# SCH_Dual_voltage_converter_2022-07-17.net
KiCad netlist of a schematic drawn in EasyEDA
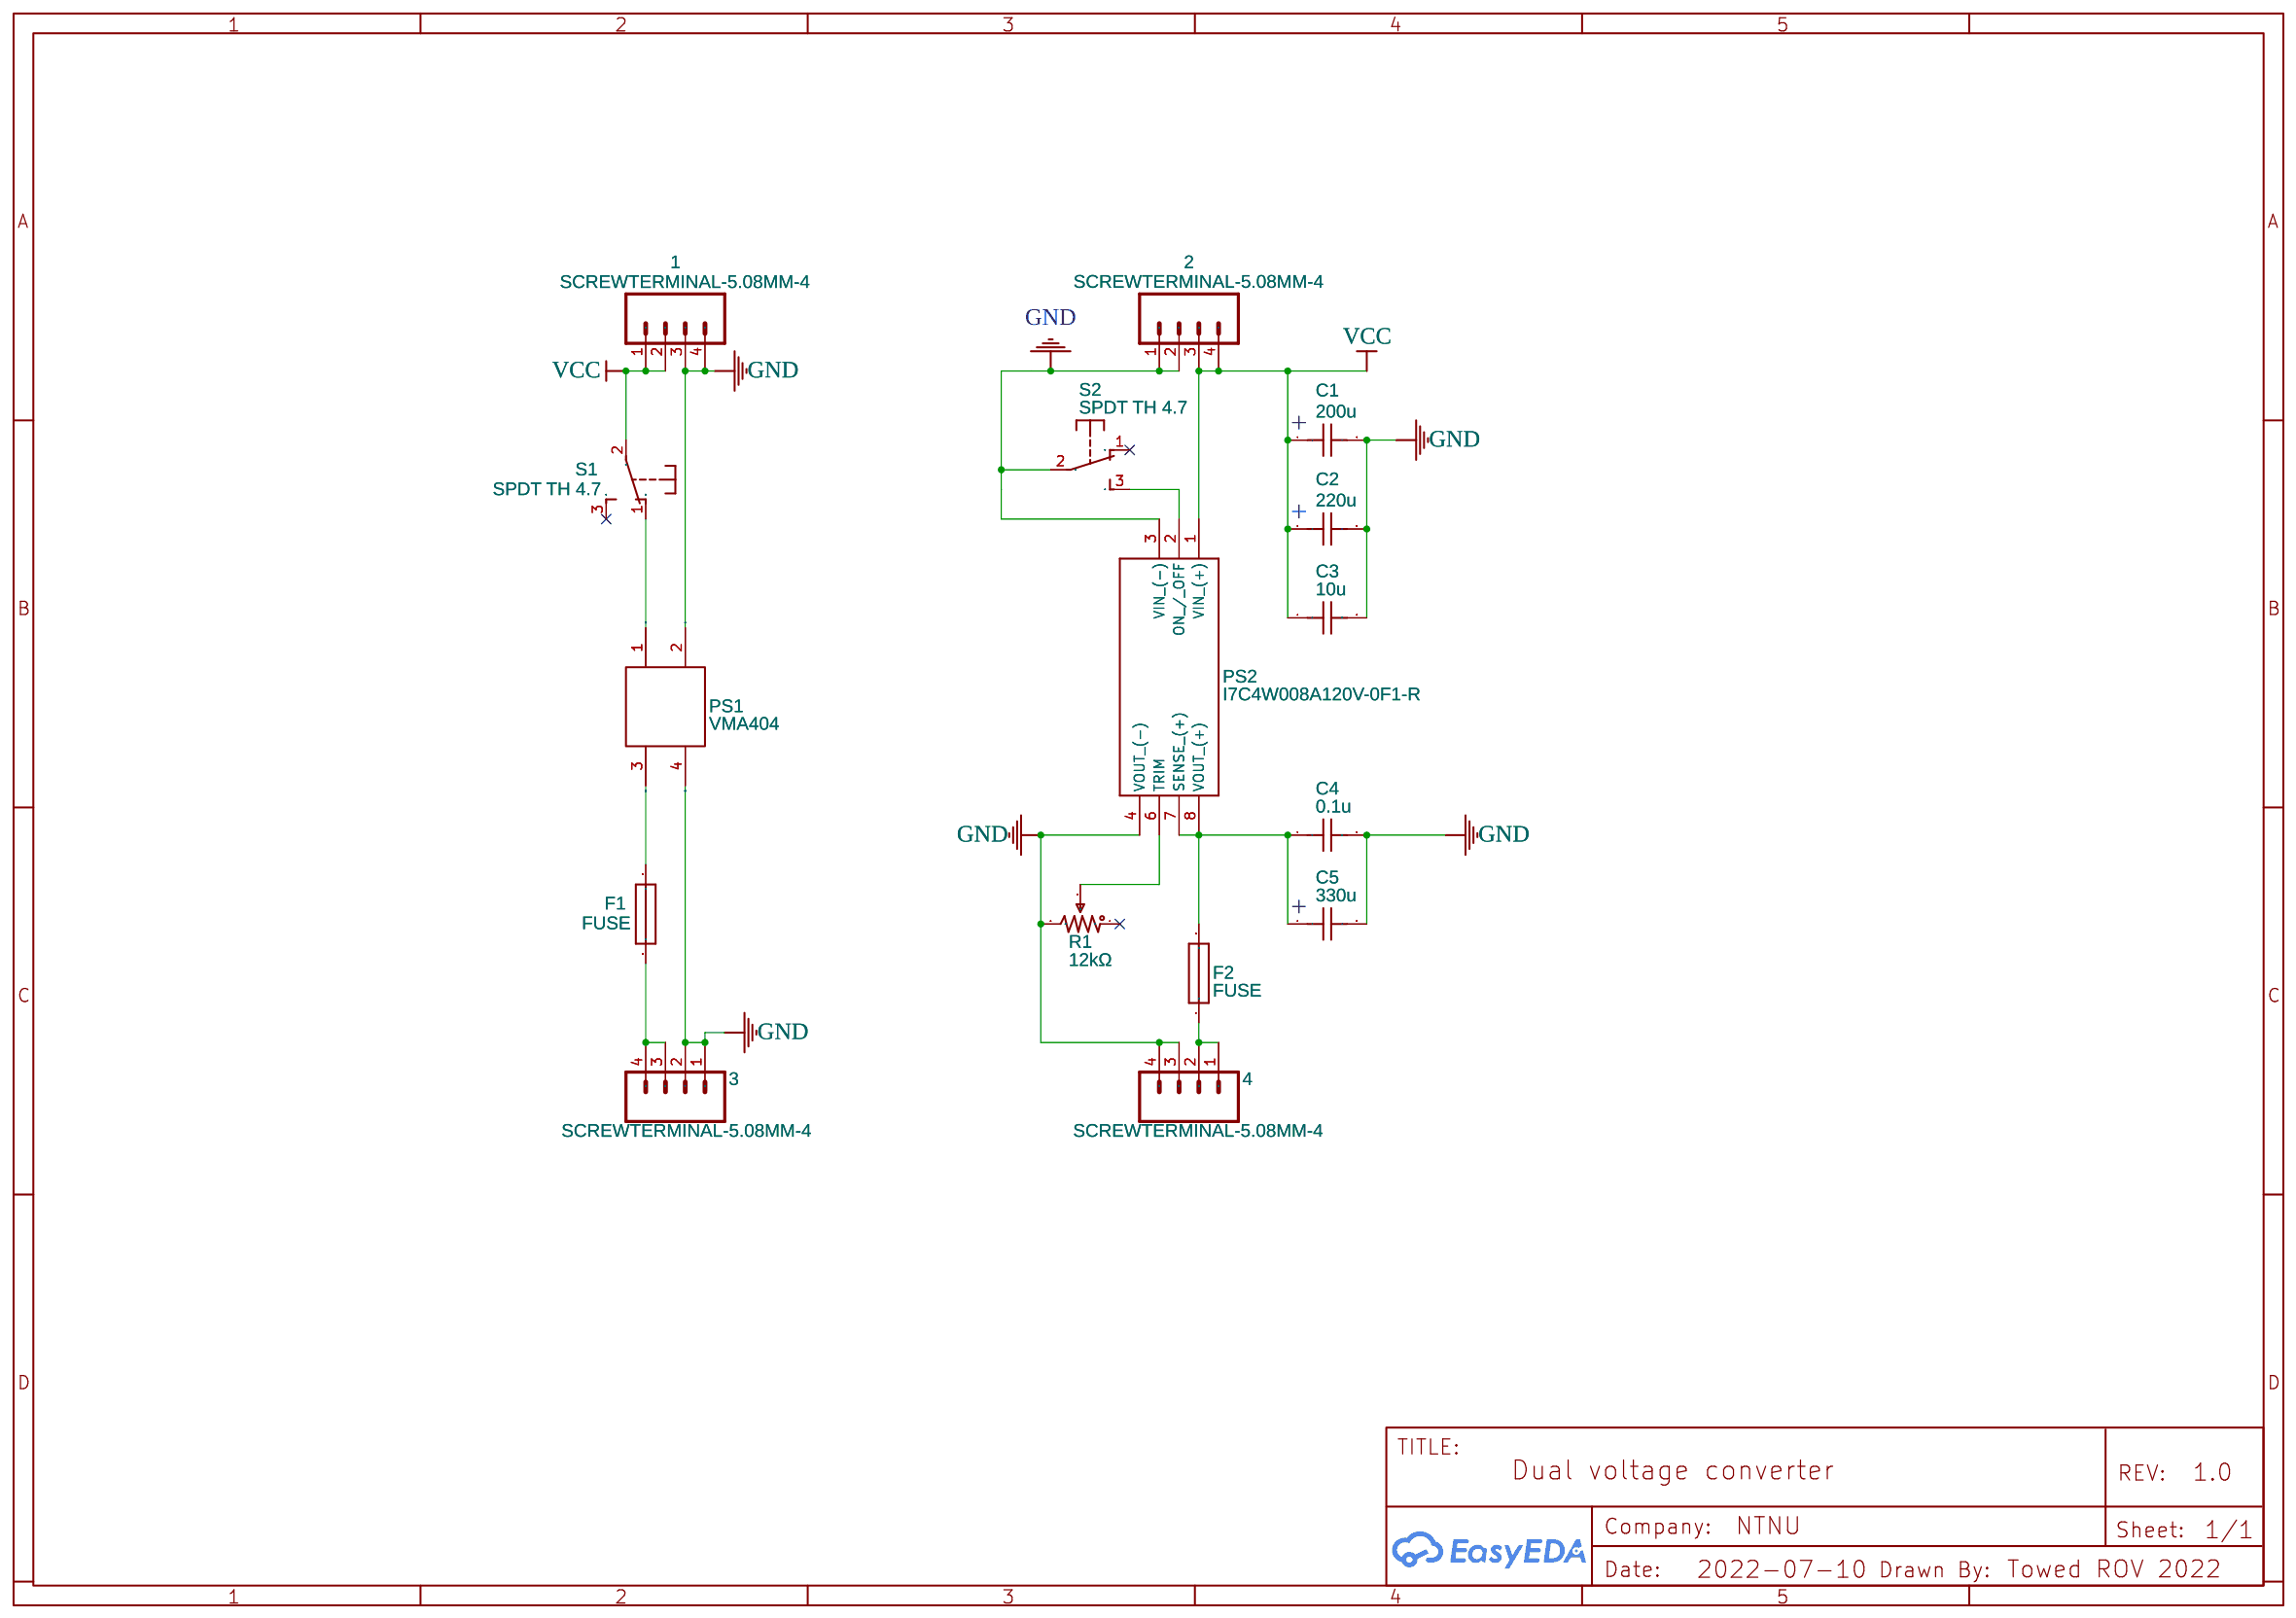
[diagram p0: schematic sheet]

(export (version "E")
  (design (tool "Eeschema 10.0.6"))
  (components
    (comp (ref "1") (value "SCREWTERMINAL-5.08MM-4") (libsource (lib "") (part "SCREWTERMINAL-5.08MM-4")))
    (comp (ref "2") (value "SCREWTERMINAL-5.08MM-4") (libsource (lib "") (part "SCREWTERMINAL-5.08MM-4")))
    (comp (ref "3") (value "SCREWTERMINAL-5.08MM-4") (libsource (lib "") (part "SCREWTERMINAL-5.08MM-4_1")))
    (comp (ref "4") (value "SCREWTERMINAL-5.08MM-4") (libsource (lib "") (part "SCREWTERMINAL-5.08MM-4_1")))
    (comp (ref "C1") (value "200u") (libsource (lib "") (part "C_0603_US")))
    (comp (ref "C2") (value "220u") (libsource (lib "") (part "C_0603_US")))
    (comp (ref "C3") (value "10u") (libsource (lib "") (part "C_0603_US_1")))
    (comp (ref "C4") (value "0.1u") (libsource (lib "") (part "C_0603_US_1")))
    (comp (ref "C5") (value "330u") (libsource (lib "") (part "C_0603_US")))
    (comp (ref "F1")
      (value "FUSE")
      (fields (field (name "BOM_Manufacturer Part") "64900001039"))
      (libsource (lib "") (part "FUSEHOLDER BLUE"))
    )
    (comp (ref "F2")
      (value "FUSE")
      (fields (field (name "BOM_Manufacturer Part") "64900001039"))
      (libsource (lib "") (part "FUSEHOLDER BLUE"))
    )
    (comp (ref "PS1")
      (value "VMA404")
      (fields
        (field (name "BOM_Manufacturer Part") "New SchematicLib")
        (field (name "BOM_Supplier Part") "1612753")
      )
      (libsource (lib "") (part "VM404Lib"))
    )
    (comp (ref "PS2") (value "I7C4W008A120V-0F1-R") (libsource (lib "") (part "I7C4W008A120V-001-R")))
    (comp (ref "R1")
      (value "12kΩ")
      (fields
        (field (name "BOM_Manufacturer Part") "3266W-1-102LF")
        (field (name "BOM_Supplier Part") "C780233")
      )
      (libsource (lib "") (part "3266W-1-102LF"))
    )
    (comp (ref "S1") (value "SPDT TH 4.7") (libsource (lib "") (part "SPDT TH 4.7")))
    (comp (ref "S2") (value "SPDT TH 4.7") (libsource (lib "") (part "SPDT TH 4.7_1")))
  )
  (nets
    (net (code "1") (name "GND") (class "Default")
      (node (ref "1") (pin "3") (pinfunction "3_3") (pintype "bidirectional"))
      (node (ref "1") (pin "4") (pinfunction "4_4") (pintype "bidirectional"))
      (node (ref "2") (pin "1") (pinfunction "1_1") (pintype "bidirectional"))
      (node (ref "2") (pin "2") (pinfunction "2_2") (pintype "bidirectional"))
      (node (ref "3") (pin "1") (pinfunction "1_1") (pintype "bidirectional"))
      (node (ref "3") (pin "2") (pinfunction "2_2") (pintype "bidirectional"))
      (node (ref "4") (pin "3") (pinfunction "3_3") (pintype "bidirectional"))
      (node (ref "4") (pin "4") (pinfunction "4_4") (pintype "bidirectional"))
      (node (ref "C1") (pin "2") (pinfunction "-_2") (pintype "unspecified"))
      (node (ref "C2") (pin "2") (pinfunction "-_2") (pintype "unspecified"))
      (node (ref "C3") (pin "2") (pinfunction "2_2") (pintype "unspecified"))
      (node (ref "C4") (pin "2") (pinfunction "2_2") (pintype "unspecified"))
      (node (ref "C5") (pin "2") (pinfunction "-_2") (pintype "unspecified"))
      (node (ref "PS1") (pin "2") (pinfunction "-VIN_2") (pintype "input"))
      (node (ref "PS1") (pin "4") (pinfunction "-VOUT_4") (pintype "output"))
      (node (ref "PS2") (pin "3") (pinfunction "VIN_(-)_3") (pintype "bidirectional"))
      (node (ref "PS2") (pin "4") (pinfunction "VOUT_(-)_4") (pintype "bidirectional"))
      (node (ref "R1") (pin "3") (pinfunction "3_3") (pintype "unspecified"))
      (node (ref "S2") (pin "2") (pinfunction "P_2") (pintype "unspecified"))
    )
    (net (code "2") (name "Net-(3-Pad3)") (class "Default")
      (node (ref "3") (pin "3") (pinfunction "3_3") (pintype "bidirectional"))
      (node (ref "3") (pin "4") (pinfunction "4_4") (pintype "bidirectional"))
      (node (ref "F1") (pin "1") (pinfunction "1_1") (pintype "bidirectional"))
    )
    (net (code "3") (name "Net-(4-Pad1)") (class "Default")
      (node (ref "4") (pin "1") (pinfunction "1_1") (pintype "bidirectional"))
      (node (ref "4") (pin "2") (pinfunction "2_2") (pintype "bidirectional"))
      (node (ref "F2") (pin "1") (pinfunction "1_1") (pintype "bidirectional"))
    )
    (net (code "4") (name "Net-(C5-+)") (class "Default")
      (node (ref "C4") (pin "1") (pinfunction "1_1") (pintype "unspecified"))
      (node (ref "C5") (pin "1") (pinfunction "+_1") (pintype "unspecified"))
      (node (ref "F2") (pin "2") (pinfunction "2_2") (pintype "bidirectional"))
      (node (ref "PS2") (pin "7") (pinfunction "SENSE_(+)_7") (pintype "bidirectional"))
      (node (ref "PS2") (pin "8") (pinfunction "VOUT_(+)_8") (pintype "bidirectional"))
    )
    (net (code "5") (name "Net-(PS1-+VIN)") (class "Default")
      (node (ref "PS1") (pin "1") (pinfunction "+VIN_1") (pintype "input"))
      (node (ref "S1") (pin "1") (pinfunction "O_1") (pintype "unspecified"))
    )
    (net (code "6") (name "Net-(PS1-+VOUT)") (class "Default")
      (node (ref "F1") (pin "2") (pinfunction "2_2") (pintype "bidirectional"))
      (node (ref "PS1") (pin "3") (pinfunction "+VOUT_3") (pintype "output"))
    )
    (net (code "7") (name "Net-(PS2-ON_{slash}_OFF)") (class "Default")
      (node (ref "PS2") (pin "2") (pinfunction "ON_/_OFF_2") (pintype "bidirectional"))
      (node (ref "S2") (pin "3") (pinfunction "S_3") (pintype "unspecified"))
    )
    (net (code "8") (name "Net-(PS2-TRIM)") (class "Default")
      (node (ref "PS2") (pin "6") (pinfunction "TRIM_6") (pintype "bidirectional"))
      (node (ref "R1") (pin "2") (pinfunction "2_2") (pintype "unspecified"))
    )
    (net (code "9") (name "VCC") (class "Default")
      (node (ref "1") (pin "1") (pinfunction "1_1") (pintype "bidirectional"))
      (node (ref "1") (pin "2") (pinfunction "2_2") (pintype "bidirectional"))
      (node (ref "2") (pin "3") (pinfunction "3_3") (pintype "bidirectional"))
      (node (ref "2") (pin "4") (pinfunction "4_4") (pintype "bidirectional"))
      (node (ref "C1") (pin "1") (pinfunction "+_1") (pintype "unspecified"))
      (node (ref "C2") (pin "1") (pinfunction "+_1") (pintype "unspecified"))
      (node (ref "C3") (pin "1") (pinfunction "1_1") (pintype "unspecified"))
      (node (ref "PS2") (pin "1") (pinfunction "VIN_(+)_1") (pintype "bidirectional"))
      (node (ref "S1") (pin "2") (pinfunction "P_2") (pintype "unspecified"))
    )
    (net (code "10") (name "unconnected-(R1-Pad1)") (class "Default")
      (node (ref "R1") (pin "1") (pinfunction "1_1") (pintype "unspecified+no_connect"))
    )
    (net (code "11") (name "unconnected-(S1-S-Pad3)") (class "Default")
      (node (ref "S1") (pin "3") (pinfunction "S_3") (pintype "unspecified+no_connect"))
    )
    (net (code "12") (name "unconnected-(S2-O-Pad1)") (class "Default")
      (node (ref "S2") (pin "1") (pinfunction "O_1") (pintype "unspecified+no_connect"))
    )
  )
)
